# NearField_E_Probe.net
KiCad netlist of a schematic drawn in Altium Designer
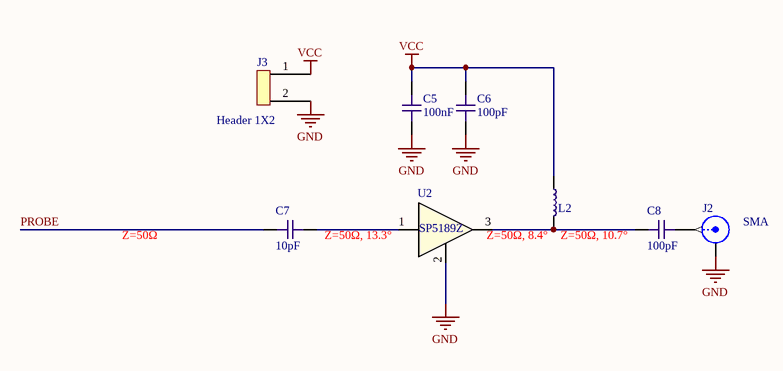
[diagram p0: NearField_E_Probe.SchDoc]

(export (version "E")
  (design (tool "Eeschema 10.0.6"))
  (components
    (comp (ref "C5")
      (value "100nF")
      (footprint "C0402-IPC")
      (description "Chip Capacitor, 0402, 100nF, 10V, X5R")
      (fields (field (name "Comment") "C0402 100nF 10V X5R"))
      (libsource (lib "Capacitors") (part "C0402 100nF 10V X5R"))
    )
    (comp (ref "C6")
      (value "100pF")
      (footprint "C0402-IPC")
      (description "Chip Capacitor, 0402, 100p, 1%, 50V, C0G")
      (fields (field (name "Comment") "C0402 100pF 50V C0G"))
      (libsource (lib "Capacitors") (part "C0402 100pF 50V C0G"))
    )
    (comp (ref "C7")
      (value "10pF")
      (footprint "C0402-IPC")
      (description "Chip Capacitor, 0402, 10pF, 50V, C0G")
      (fields (field (name "Comment") "C0402 10pF 50V C0G"))
      (libsource (lib "Capacitors") (part "C0402 10pF 50V C0G"))
    )
    (comp (ref "C8")
      (value "100pF")
      (footprint "C0402-IPC")
      (description "Chip Capacitor, 0402, 100p, 1%, 50V, C0G")
      (fields (field (name "Comment") "C0402 100pF 50V C0G"))
      (libsource (lib "Capacitors") (part "C0402 100pF 50V C0G"))
    )
    (comp (ref "J2")
      (value "SMA")
      (footprint "SMA Edge Launch (Horizontal)")
      (description "SMA Connector")
      (libsource (lib "Connectors") (part "SMA"))
    )
    (comp (ref "J3")
      (value "Header 1X2")
      (footprint "Header 1x2 TH Pitch 2.54mm")
      (libsource (lib "Connectors") (part "Header 1X2"))
    )
    (comp (ref "L2")
      (value "LQW15AN47NG8ZD")
      (footprint "L0402-Murata-WW-High-Density")
      (description "47nH Unshielded Wirewound Inductor 440mA 648mOhm Max 0402 (1005 Metric)")
      (libsource (lib "Inductors") (part "L0402 47nH High-Q"))
    )
    (comp (ref "U2")
      (value "SP5189Z")
      (footprint "RF Components:SOT-89")
      (description "RF Amplifier .05-4GHz SSG 12.8dB NF .8dB GaAs")
      (libsource (lib "RF Components") (part "SPF5189Z"))
    )
  )
  (nets
    (net (code "1") (name "/PROBE") (class "Default") (node (ref "C7") (pin "1") (pintype "passive")))
    (net (code "2") (name "GND") (class "Default")
      (node (ref "C5") (pin "1") (pintype "passive"))
      (node (ref "C6") (pin "1") (pintype "passive"))
      (node (ref "J2") (pin "2") (pinfunction "Y_2") (pintype "power_in"))
      (node (ref "J3") (pin "2") (pintype "passive"))
      (node (ref "U2") (pin "2") (pinfunction "GND_2") (pintype "passive"))
    )
    (net (code "3") (name "Net-(J2-X)") (class "Default")
      (node (ref "C8") (pin "2") (pintype "passive"))
      (node (ref "J2") (pin "1") (pinfunction "X_1") (pintype "output"))
    )
    (net (code "4") (name "Net-(U2-RFIN)") (class "Default")
      (node (ref "C7") (pin "2") (pintype "passive"))
      (node (ref "U2") (pin "1") (pinfunction "RFIN_1") (pintype "passive"))
    )
    (net (code "5") (name "Net-(U2-RFOUT{slash}DCBIAS)") (class "Default")
      (node (ref "C8") (pin "1") (pintype "passive"))
      (node (ref "L2") (pin "2") (pintype "passive"))
      (node (ref "U2") (pin "3") (pinfunction "RFOUT/DCBIAS_3") (pintype "passive"))
    )
    (net (code "6") (name "VCC") (class "Default")
      (node (ref "C5") (pin "2") (pintype "passive"))
      (node (ref "C6") (pin "2") (pintype "passive"))
      (node (ref "J3") (pin "1") (pintype "passive"))
      (node (ref "L2") (pin "1") (pintype "passive"))
    )
  )
)
